# ETH_Interface.net
KiCad netlist of a schematic drawn in Altium Designer
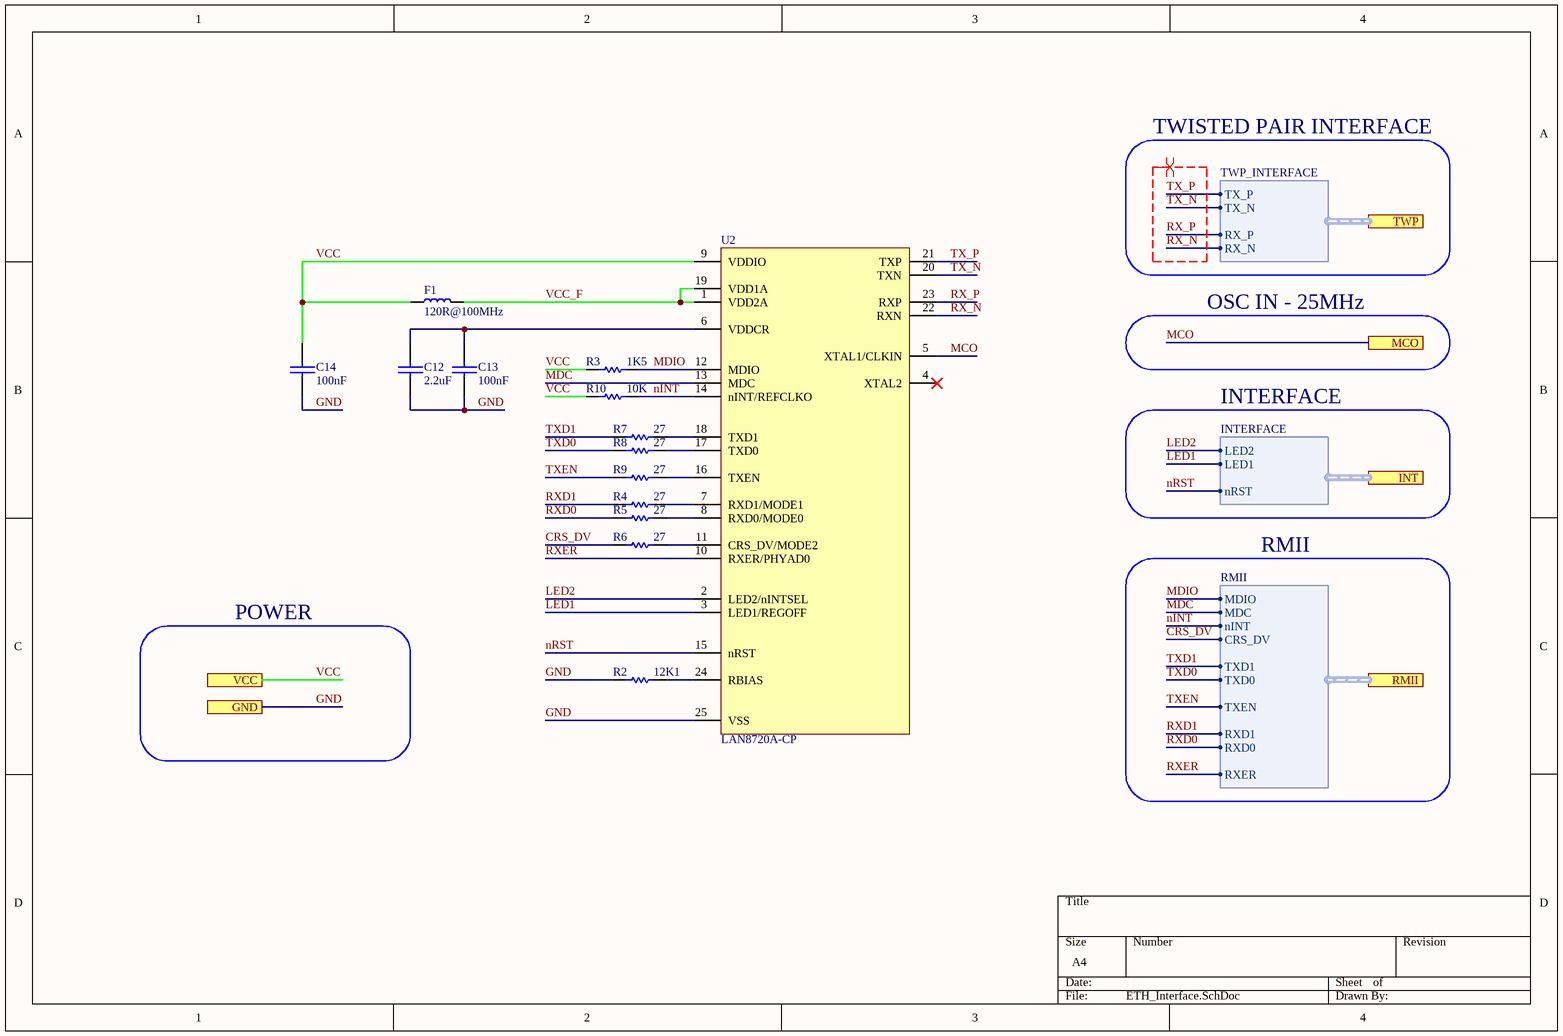
[diagram p0: ETH_Interface.SchDoc]

(export (version "E")
  (design (tool "Eeschema 10.0.6"))
  (components
    (comp (ref "C12")
      (value "2.2uF")
      (footprint "0603-CAP-TDK")
      (libsource (lib "LIB2022 - Passives") (part "CAP-SMD"))
    )
    (comp (ref "C13")
      (value "100nF")
      (footprint "0402-CAP-TDK")
      (libsource (lib "LIB2022 - Passives") (part "CAP-SMD"))
    )
    (comp (ref "C14")
      (value "100nF")
      (footprint "0402-CAP-TDK")
      (libsource (lib "LIB2022 - Passives") (part "CAP-SMD"))
    )
    (comp (ref "F1")
      (value "120R@100MHz")
      (footprint "0603-IND-MURATA")
      (libsource (lib "LIB2022 - Filters") (part "BLM18BD121SN1D"))
    )
    (comp (ref "R2")
      (value "12K1")
      (footprint "0402-RES-PANASONIC")
      (libsource (lib "LIB2022 - Passives") (part "RES-SMD"))
    )
    (comp (ref "R3")
      (value "1K5")
      (footprint "0402-RES-PANASONIC")
      (libsource (lib "LIB2022 - Passives") (part "RES-SMD"))
    )
    (comp (ref "R4")
      (value "27")
      (footprint "0402-RES-PANASONIC")
      (libsource (lib "LIB2022 - Passives") (part "RES-SMD"))
    )
    (comp (ref "R5")
      (value "27")
      (footprint "0402-RES-PANASONIC")
      (libsource (lib "LIB2022 - Passives") (part "RES-SMD"))
    )
    (comp (ref "R6")
      (value "27")
      (footprint "0402-RES-PANASONIC")
      (libsource (lib "LIB2022 - Passives") (part "RES-SMD"))
    )
    (comp (ref "R7")
      (value "27")
      (footprint "0402-RES-PANASONIC")
      (libsource (lib "LIB2022 - Passives") (part "RES-SMD"))
    )
    (comp (ref "R8")
      (value "27")
      (footprint "0402-RES-PANASONIC")
      (libsource (lib "LIB2022 - Passives") (part "RES-SMD"))
    )
    (comp (ref "R9")
      (value "27")
      (footprint "0402-RES-PANASONIC")
      (libsource (lib "LIB2022 - Passives") (part "RES-SMD"))
    )
    (comp (ref "R10")
      (value "10K")
      (footprint "0402-RES-PANASONIC")
      (libsource (lib "LIB2022 - Passives") (part "RES-SMD"))
    )
    (comp (ref "U2")
      (value "LAN8720A-CP")
      (footprint "MC 24-QFN-PUNCH")
      (libsource (lib "LIB2022 - ICs") (part "LAN8720A-CP"))
    )
  )
  (nets
    (net (code "4") (name "/CRS_DV") (class "Default")
      (node (ref "R6") (pin "1") (pinfunction "1_1") (pintype "passive"))
    )
    (net (code "5") (name "/GND") (class "Default")
      (node (ref "C12") (pin "1") (pinfunction "1_1") (pintype "passive"))
      (node (ref "C13") (pin "1") (pinfunction "1_1") (pintype "passive"))
      (node (ref "C14") (pin "1") (pinfunction "1_1") (pintype "passive"))
      (node (ref "R2") (pin "1") (pinfunction "1_1") (pintype "passive"))
      (node (ref "U2") (pin "25") (pinfunction "VSS_25") (pintype "passive"))
    )
    (net (code "6") (name "/LED1") (class "Default")
      (node (ref "U2") (pin "3") (pinfunction "LED1/REGOFF_3") (pintype "passive"))
    )
    (net (code "7") (name "/LED2") (class "Default")
      (node (ref "U2") (pin "2") (pinfunction "LED2/nINTSEL_2") (pintype "passive"))
    )
    (net (code "8") (name "/MCO") (class "Default")
      (node (ref "U2") (pin "5") (pinfunction "XTAL1/CLKIN_5") (pintype "passive"))
    )
    (net (code "9") (name "/MDC") (class "Default")
      (node (ref "U2") (pin "13") (pinfunction "MDC_13") (pintype "passive"))
    )
    (net (code "10") (name "/MDIO") (class "Default")
      (node (ref "R3") (pin "2") (pinfunction "2_2") (pintype "passive"))
      (node (ref "U2") (pin "12") (pinfunction "MDIO_12") (pintype "passive"))
    )
    (net (code "11") (name "/RXD0") (class "Default")
      (node (ref "R5") (pin "1") (pinfunction "1_1") (pintype "passive"))
    )
    (net (code "12") (name "/RXD1") (class "Default")
      (node (ref "R4") (pin "1") (pinfunction "1_1") (pintype "passive"))
    )
    (net (code "13") (name "/RXER") (class "Default")
      (node (ref "U2") (pin "10") (pinfunction "RXER/PHYAD0_10") (pintype "passive"))
    )
    (net (code "14") (name "/RX_N") (class "Default")
      (node (ref "U2") (pin "22") (pinfunction "RXN_22") (pintype "passive"))
    )
    (net (code "15") (name "/RX_P") (class "Default")
      (node (ref "U2") (pin "23") (pinfunction "RXP_23") (pintype "passive"))
    )
    (net (code "16") (name "/TXD0") (class "Default")
      (node (ref "R8") (pin "1") (pinfunction "1_1") (pintype "passive"))
    )
    (net (code "17") (name "/TXD1") (class "Default")
      (node (ref "R7") (pin "1") (pinfunction "1_1") (pintype "passive"))
    )
    (net (code "18") (name "/TXEN") (class "Default")
      (node (ref "R9") (pin "1") (pinfunction "1_1") (pintype "passive"))
    )
    (net (code "19") (name "/TX_N") (class "Default")
      (node (ref "U2") (pin "20") (pinfunction "TXN_20") (pintype "passive"))
    )
    (net (code "20") (name "/TX_P") (class "Default")
      (node (ref "U2") (pin "21") (pinfunction "TXP_21") (pintype "passive"))
    )
    (net (code "21") (name "/VCC") (class "Default")
      (node (ref "C14") (pin "2") (pinfunction "2_2") (pintype "passive"))
      (node (ref "F1") (pin "2") (pinfunction "2_2") (pintype "passive"))
      (node (ref "R10") (pin "1") (pinfunction "1_1") (pintype "passive"))
      (node (ref "R3") (pin "1") (pinfunction "1_1") (pintype "passive"))
      (node (ref "U2") (pin "9") (pinfunction "VDDIO_9") (pintype "passive"))
    )
    (net (code "22") (name "/VCC_F") (class "Default")
      (node (ref "F1") (pin "1") (pinfunction "1_1") (pintype "passive"))
      (node (ref "U2") (pin "1") (pinfunction "VDD2A_1") (pintype "passive"))
      (node (ref "U2") (pin "19") (pinfunction "VDD1A_19") (pintype "passive"))
    )
    (net (code "23") (name "/nINT") (class "Default")
      (node (ref "R10") (pin "2") (pinfunction "2_2") (pintype "passive"))
      (node (ref "U2") (pin "14") (pinfunction "nINT/REFCLKO_14") (pintype "passive"))
    )
    (net (code "24") (name "/nRST") (class "Default")
      (node (ref "U2") (pin "15") (pinfunction "nRST_15") (pintype "passive"))
    )
    (net (code "28") (name "Net-(U2-CRS_DV{slash}MODE2)") (class "Default")
      (node (ref "R6") (pin "2") (pinfunction "2_2") (pintype "passive"))
      (node (ref "U2") (pin "11") (pinfunction "CRS_DV/MODE2_11") (pintype "passive"))
    )
    (net (code "29") (name "Net-(U2-RBIAS)") (class "Default")
      (node (ref "R2") (pin "2") (pinfunction "2_2") (pintype "passive"))
      (node (ref "U2") (pin "24") (pinfunction "RBIAS_24") (pintype "passive"))
    )
    (net (code "30") (name "Net-(U2-RXD0{slash}MODE0)") (class "Default")
      (node (ref "R5") (pin "2") (pinfunction "2_2") (pintype "passive"))
      (node (ref "U2") (pin "8") (pinfunction "RXD0/MODE0_8") (pintype "passive"))
    )
    (net (code "31") (name "Net-(U2-RXD1{slash}MODE1)") (class "Default")
      (node (ref "R4") (pin "2") (pinfunction "2_2") (pintype "passive"))
      (node (ref "U2") (pin "7") (pinfunction "RXD1/MODE1_7") (pintype "passive"))
    )
    (net (code "32") (name "Net-(U2-TXD0)") (class "Default")
      (node (ref "R8") (pin "2") (pinfunction "2_2") (pintype "passive"))
      (node (ref "U2") (pin "17") (pinfunction "TXD0_17") (pintype "passive"))
    )
    (net (code "33") (name "Net-(U2-TXD1)") (class "Default")
      (node (ref "R7") (pin "2") (pinfunction "2_2") (pintype "passive"))
      (node (ref "U2") (pin "18") (pinfunction "TXD1_18") (pintype "passive"))
    )
    (net (code "34") (name "Net-(U2-TXEN)") (class "Default")
      (node (ref "R9") (pin "2") (pinfunction "2_2") (pintype "passive"))
      (node (ref "U2") (pin "16") (pinfunction "TXEN_16") (pintype "passive"))
    )
    (net (code "35") (name "Net-(U2-VDDCR)") (class "Default")
      (node (ref "C12") (pin "2") (pinfunction "2_2") (pintype "passive"))
      (node (ref "C13") (pin "2") (pinfunction "2_2") (pintype "passive"))
      (node (ref "U2") (pin "6") (pinfunction "VDDCR_6") (pintype "passive"))
    )
    (net (code "36") (name "unconnected-(U2-XTAL2-Pad4)") (class "Default")
      (node (ref "U2") (pin "4") (pinfunction "XTAL2_4") (pintype "passive+no_connect"))
    )
  )
)
